# ISP.net
KiCad netlist of a schematic drawn in EAGLE
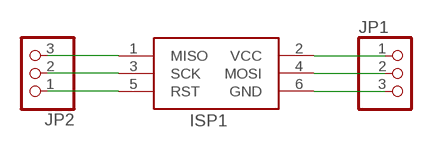
[diagram p0: schematic, sheet 1]

(export (version "E")
  (design (tool "Eeschema 10.0.6"))
  (components
    (comp (ref "ISP1")
      (value "AVRISP-6")
      (footprint "eagle-import:AVRISP")
      (libsource (lib "eagle-import") (part "AVRISP-6"))
    )
    (comp (ref "JP1")
      (value "PINHD-1X3")
      (footprint "eagle-import:1X03")
      (libsource (lib "eagle-import") (part "PINHD-1X3"))
    )
    (comp (ref "JP2")
      (value "PINHD-1X3")
      (footprint "eagle-import:1X03")
      (libsource (lib "eagle-import") (part "PINHD-1X3"))
    )
  )
  (nets
    (net (code "1") (name "Net-(ISP1-GND)") (class "Default")
      (node (ref "ISP1") (pin "6") (pinfunction "GND_6") (pintype "power_in"))
      (node (ref "JP1") (pin "3") (pinfunction "3_3") (pintype "passive"))
    )
    (net (code "2") (name "Net-(ISP1-MISO)") (class "Default")
      (node (ref "ISP1") (pin "1") (pinfunction "MISO_1") (pintype "input"))
      (node (ref "JP2") (pin "3") (pinfunction "3_3") (pintype "passive"))
    )
    (net (code "3") (name "Net-(ISP1-MOSI)") (class "Default")
      (node (ref "ISP1") (pin "4") (pinfunction "MOSI_4") (pintype "output"))
      (node (ref "JP1") (pin "2") (pinfunction "2_2") (pintype "passive"))
    )
    (net (code "4") (name "Net-(ISP1-RST)") (class "Default")
      (node (ref "ISP1") (pin "5") (pinfunction "RST_5") (pintype "output"))
      (node (ref "JP2") (pin "1") (pinfunction "1_1") (pintype "passive"))
    )
    (net (code "5") (name "Net-(ISP1-SCK)") (class "Default")
      (node (ref "ISP1") (pin "3") (pinfunction "SCK_3") (pintype "output"))
      (node (ref "JP2") (pin "2") (pinfunction "2_2") (pintype "passive"))
    )
    (net (code "6") (name "Net-(ISP1-VCC)") (class "Default")
      (node (ref "ISP1") (pin "2") (pinfunction "VCC_2") (pintype "power_in"))
      (node (ref "JP1") (pin "1") (pinfunction "1_1") (pintype "passive"))
    )
  )
)
